# LDO-Schematic.net
KiCad netlist of a schematic drawn in Altium Designer
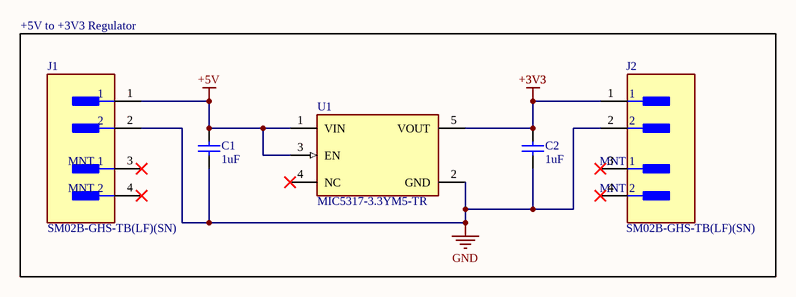
[diagram p0: LDO-Schematic.SchDoc]

(export (version "E")
  (design (tool "Eeschema 10.0.6"))
  (components
    (comp (ref "C1")
      (value "1uF")
      (footprint "CAPC2013X145X50NL20T20")
      (fields (field (name "PART NUMBER") "VJ0805Y105KXQRW1BC") (field (name "MANUFACTURER") "Vitramon"))
      (libsource (lib "Altium Content Vault") (part "CAP"))
    )
    (comp (ref "C2")
      (value "1uF")
      (footprint "CAPC2013X145X50NL20T20")
      (fields (field (name "PART NUMBER") "VJ0805Y105KXQRW1BC") (field (name "MANUFACTURER") "Vitramon"))
      (libsource (lib "Altium Content Vault") (part "CAP"))
    )
    (comp (ref "J1")
      (value "SM02B-GHS-TB(LF)(SN)")
      (footprint "FP-SM02B-GHS-TB_LF_SN-MFG")
      (description "CONN HEADER SMD R/A 2POS 1.25MM")
      (libsource (lib "") (part "56ec3178a87b3978bdc1b3682cd516a_1"))
    )
    (comp (ref "J2")
      (value "SM02B-GHS-TB(LF)(SN)")
      (footprint "FP-SM02B-GHS-TB_LF_SN-MFG")
      (description "CONN HEADER SMD R/A 2POS 1.25MM")
      (libsource (lib "Altium Content Vault") (part "56ec3178a87b3978bdc1b3682cd516a"))
    )
    (comp (ref "U1")
      (value "MIC5317-3.3YM5-TR")
      (footprint "FP-SOT23-5LD-PL-1-MFG")
      (description "IC REG LINEAR 3.3V 150MA SOT23-5")
      (libsource (lib "Altium Content Vault") (part "0a093dae7315cdc977fd108dde87457"))
    )
  )
  (nets
    (net (code "1") (name "+3V3") (class "Default")
      (node (ref "C2") (pin "2") (pinfunction "2_2") (pintype "passive"))
      (node (ref "J2") (pin "1") (pinfunction "1_1") (pintype "passive"))
      (node (ref "U1") (pin "5") (pinfunction "VOUT_5") (pintype "power_in"))
    )
    (net (code "2") (name "+5V") (class "Default")
      (node (ref "C1") (pin "2") (pinfunction "2_2") (pintype "passive"))
      (node (ref "J1") (pin "1") (pinfunction "1_1") (pintype "passive"))
      (node (ref "U1") (pin "1") (pinfunction "VIN_1") (pintype "power_in"))
      (node (ref "U1") (pin "3") (pinfunction "EN_3") (pintype "input"))
    )
    (net (code "3") (name "GND") (class "Default")
      (node (ref "C1") (pin "1") (pinfunction "1_1") (pintype "passive"))
      (node (ref "C2") (pin "1") (pinfunction "1_1") (pintype "passive"))
      (node (ref "J1") (pin "2") (pinfunction "2_2") (pintype "passive"))
      (node (ref "J2") (pin "2") (pinfunction "2_2") (pintype "passive"))
      (node (ref "U1") (pin "2") (pinfunction "GND_2") (pintype "power_in"))
    )
    (net (code "4") (name "unconnected-(J1-MNT_1-Pad3)") (class "Default")
      (node (ref "J1") (pin "3") (pinfunction "MNT_1_3") (pintype "passive+no_connect"))
    )
    (net (code "5") (name "unconnected-(J1-MNT_2-Pad4)") (class "Default")
      (node (ref "J1") (pin "4") (pinfunction "MNT_2_4") (pintype "passive+no_connect"))
    )
    (net (code "6") (name "unconnected-(J2-MNT_1-Pad3)") (class "Default")
      (node (ref "J2") (pin "3") (pinfunction "MNT_1_3") (pintype "passive+no_connect"))
    )
    (net (code "7") (name "unconnected-(J2-MNT_2-Pad4)") (class "Default")
      (node (ref "J2") (pin "4") (pinfunction "MNT_2_4") (pintype "passive+no_connect"))
    )
    (net (code "8") (name "unconnected-(U1-NC-Pad4)") (class "Default")
      (node (ref "U1") (pin "4") (pinfunction "NC_4") (pintype "passive+no_connect"))
    )
  )
)
